# TinyPICO_FeatherWing.net
KiCad netlist of a schematic drawn in EAGLE
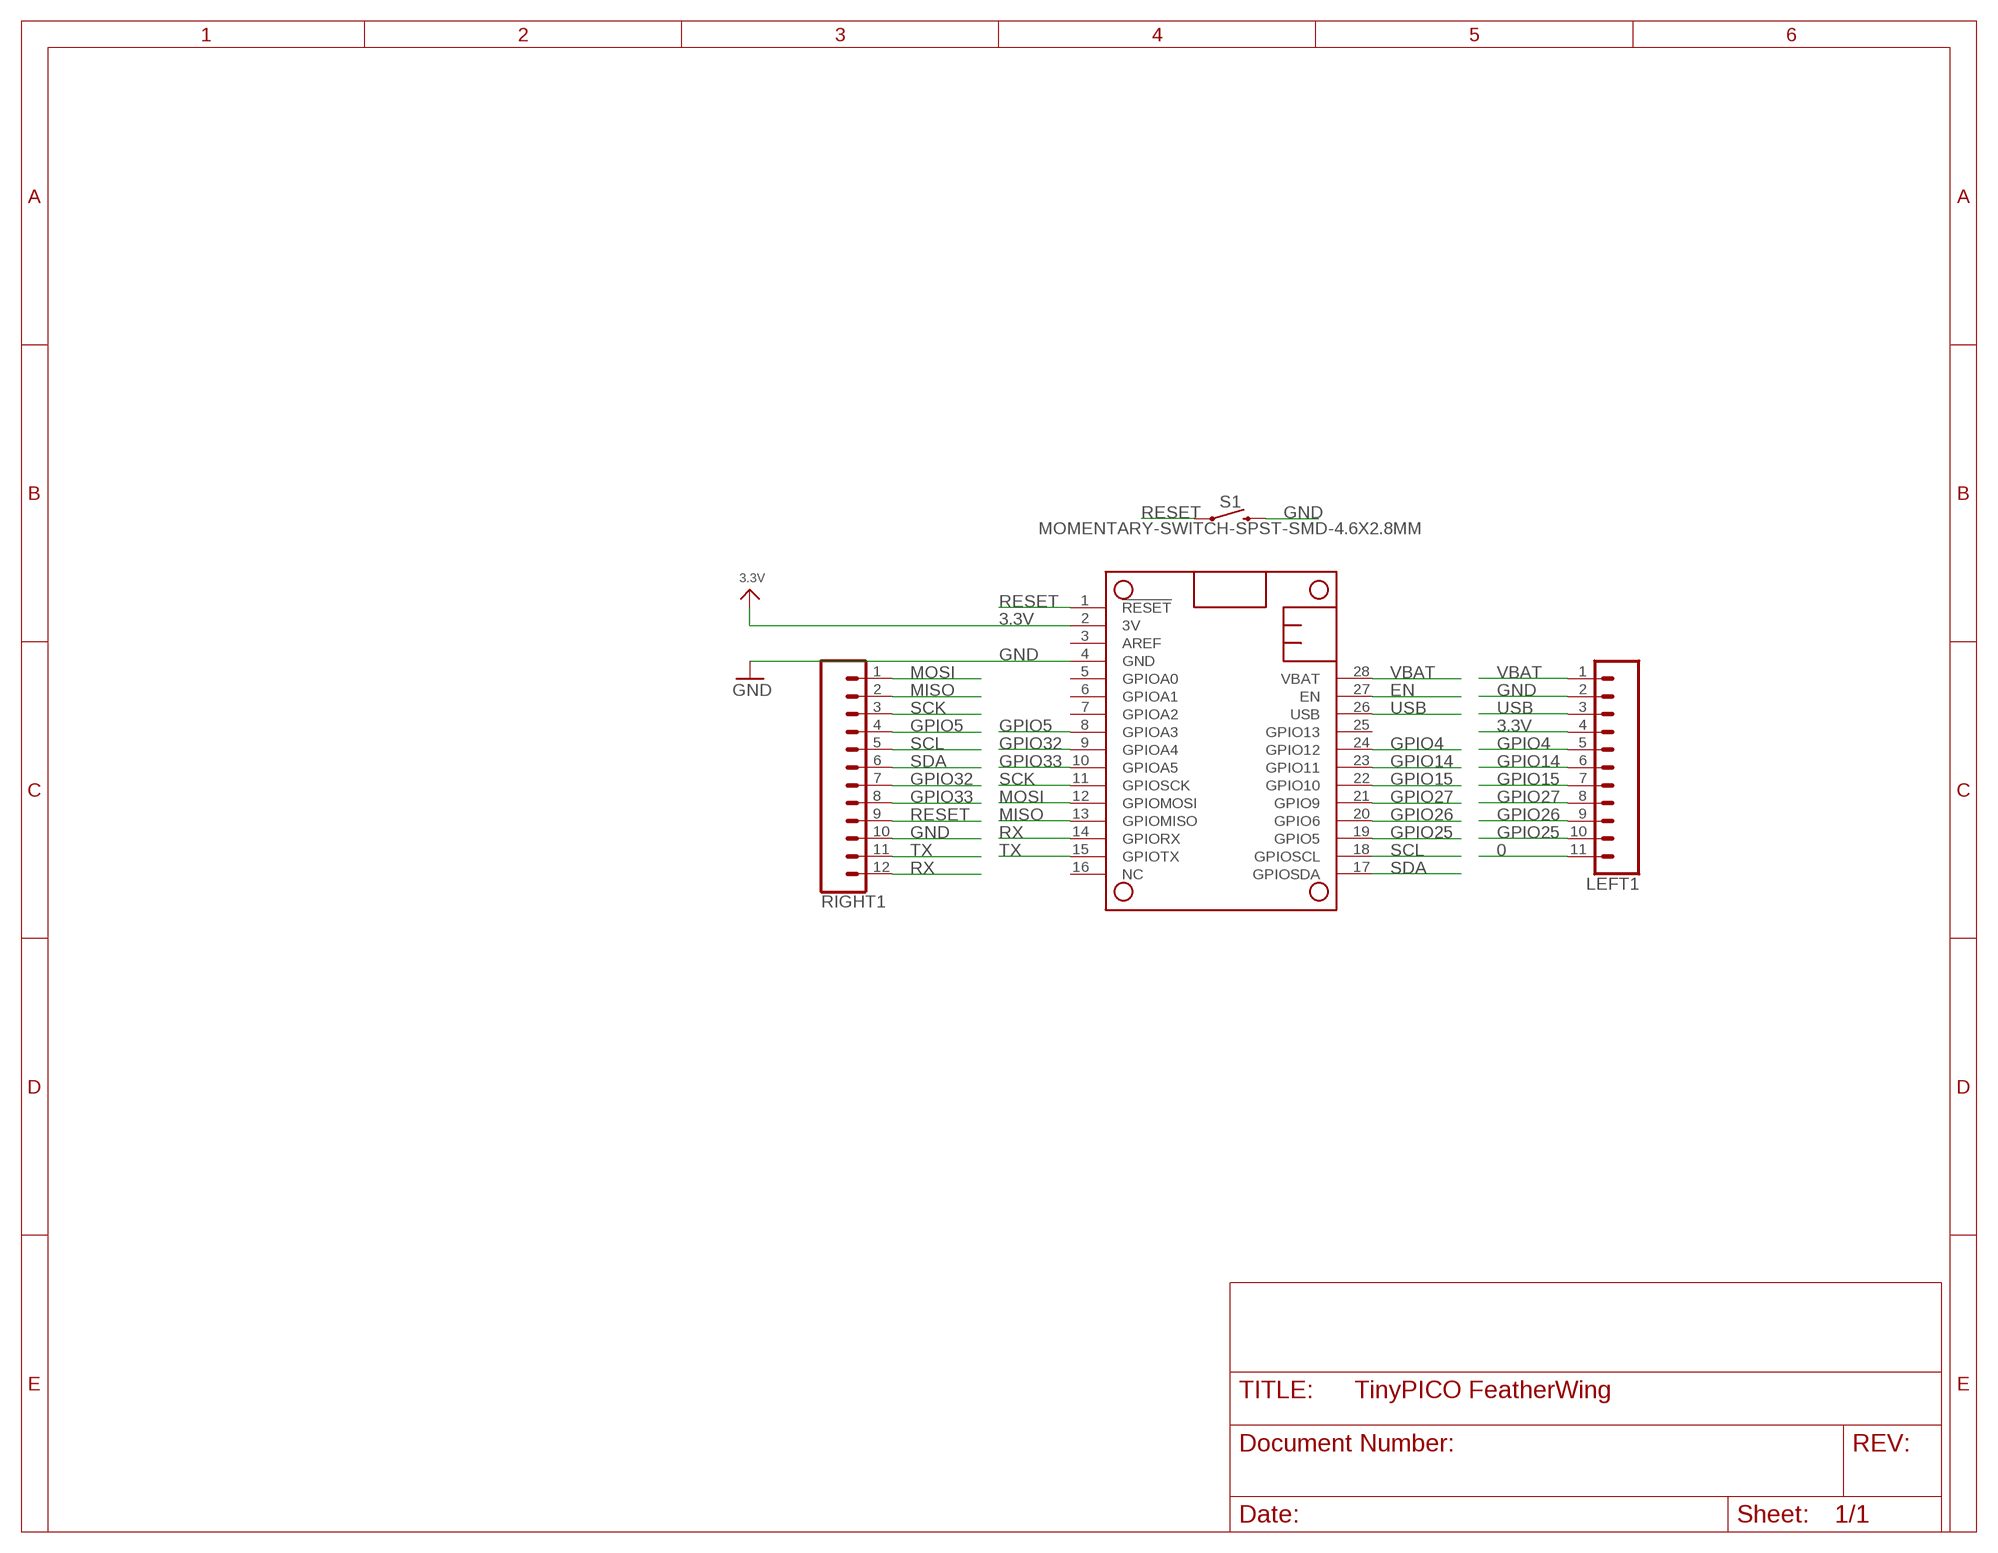
[diagram p0: schematic, sheet 1]

(export (version "E")
  (design (tool "Eeschema 10.0.6"))
  (components
    (comp (ref "LEFT1")
      (value "CONN_11")
      (footprint "eagle-import:1X11")
      (libsource (lib "eagle-import") (part "CONN_11"))
    )
    (comp (ref "MS2")
      (value "FEATHERWING")
      (footprint "eagle-import:FEATHERWING")
      (libsource (lib "eagle-import") (part "FEATHERWING"))
    )
    (comp (ref "RIGHT1")
      (value "CONN_12")
      (footprint "eagle-import:1X12")
      (libsource (lib "eagle-import") (part "CONN_12"))
    )
    (comp (ref "S1")
      (value "MOMENTARY-SWITCH-SPST-SMD-4.6X2.8MM")
      (footprint "eagle-import:TACTILE_SWITCH_SMD_4.6X2.8MM")
      (libsource (lib "eagle-import") (part "MOMENTARY-SWITCH-SPST-SMD-4.6X2.8MM"))
    )
  )
  (nets
    (net (code "1") (name "/0") (class "Default")
      (node (ref "LEFT1") (pin "11") (pinfunction "11_11") (pintype "passive"))
    )
    (net (code "2") (name "/EN") (class "Default")
      (node (ref "MS2") (pin "27") (pinfunction "EN_27") (pintype "passive"))
    )
    (net (code "3") (name "/GPIO4") (class "Default")
      (node (ref "LEFT1") (pin "5") (pinfunction "5_5") (pintype "passive"))
      (node (ref "MS2") (pin "24") (pinfunction "GPIO12_24") (pintype "bidirectional"))
    )
    (net (code "4") (name "/GPIO5") (class "Default")
      (node (ref "MS2") (pin "8") (pinfunction "GPIOA3_8") (pintype "bidirectional"))
      (node (ref "RIGHT1") (pin "4") (pinfunction "4_4") (pintype "passive"))
    )
    (net (code "5") (name "/GPIO14") (class "Default")
      (node (ref "LEFT1") (pin "6") (pinfunction "6_6") (pintype "passive"))
      (node (ref "MS2") (pin "23") (pinfunction "GPIO11_23") (pintype "bidirectional"))
    )
    (net (code "6") (name "/GPIO15") (class "Default")
      (node (ref "LEFT1") (pin "7") (pinfunction "7_7") (pintype "passive"))
      (node (ref "MS2") (pin "22") (pinfunction "GPIO10_22") (pintype "bidirectional"))
    )
    (net (code "7") (name "/GPIO25") (class "Default")
      (node (ref "LEFT1") (pin "10") (pinfunction "10_10") (pintype "passive"))
      (node (ref "MS2") (pin "19") (pinfunction "GPIO5_19") (pintype "bidirectional"))
    )
    (net (code "8") (name "/GPIO26") (class "Default")
      (node (ref "LEFT1") (pin "9") (pinfunction "9_9") (pintype "passive"))
      (node (ref "MS2") (pin "20") (pinfunction "GPIO6_20") (pintype "bidirectional"))
    )
    (net (code "9") (name "/GPIO27") (class "Default")
      (node (ref "LEFT1") (pin "8") (pinfunction "8_8") (pintype "passive"))
      (node (ref "MS2") (pin "21") (pinfunction "GPIO9_21") (pintype "bidirectional"))
    )
    (net (code "10") (name "/GPIO32") (class "Default")
      (node (ref "MS2") (pin "9") (pinfunction "GPIOA4_9") (pintype "bidirectional"))
      (node (ref "RIGHT1") (pin "7") (pinfunction "7_7") (pintype "passive"))
    )
    (net (code "11") (name "/GPIO33") (class "Default")
      (node (ref "MS2") (pin "10") (pinfunction "GPIOA5_10") (pintype "bidirectional"))
      (node (ref "RIGHT1") (pin "8") (pinfunction "8_8") (pintype "passive"))
    )
    (net (code "12") (name "/MISO") (class "Default")
      (node (ref "MS2") (pin "13") (pinfunction "GPIOMISO_13") (pintype "bidirectional"))
      (node (ref "RIGHT1") (pin "2") (pinfunction "2_2") (pintype "passive"))
    )
    (net (code "13") (name "/MOSI") (class "Default")
      (node (ref "MS2") (pin "12") (pinfunction "GPIOMOSI_12") (pintype "bidirectional"))
      (node (ref "RIGHT1") (pin "1") (pinfunction "1_1") (pintype "passive"))
    )
    (net (code "14") (name "/RESET") (class "Default")
      (node (ref "MS2") (pin "1") (pinfunction "~{RESET}_1") (pintype "input"))
      (node (ref "RIGHT1") (pin "9") (pinfunction "9_9") (pintype "passive"))
      (node (ref "S1") (pin "1") (pinfunction "1_1") (pintype "passive"))
      (node (ref "S1") (pin "2") (pinfunction "1_2") (pintype "passive"))
    )
    (net (code "15") (name "/RX") (class "Default")
      (node (ref "MS2") (pin "14") (pinfunction "GPIORX_14") (pintype "bidirectional"))
      (node (ref "RIGHT1") (pin "12") (pinfunction "12_12") (pintype "passive"))
    )
    (net (code "16") (name "/SCK") (class "Default")
      (node (ref "MS2") (pin "11") (pinfunction "GPIOSCK_11") (pintype "bidirectional"))
      (node (ref "RIGHT1") (pin "3") (pinfunction "3_3") (pintype "passive"))
    )
    (net (code "17") (name "/SCL") (class "Default")
      (node (ref "MS2") (pin "18") (pinfunction "GPIOSCL_18") (pintype "bidirectional"))
      (node (ref "RIGHT1") (pin "5") (pinfunction "5_5") (pintype "passive"))
    )
    (net (code "18") (name "/SDA") (class "Default")
      (node (ref "MS2") (pin "17") (pinfunction "GPIOSDA_17") (pintype "bidirectional"))
      (node (ref "RIGHT1") (pin "6") (pinfunction "6_6") (pintype "passive"))
    )
    (net (code "19") (name "/TX") (class "Default")
      (node (ref "MS2") (pin "15") (pinfunction "GPIOTX_15") (pintype "bidirectional"))
      (node (ref "RIGHT1") (pin "11") (pinfunction "11_11") (pintype "passive"))
    )
    (net (code "20") (name "/USB") (class "Default")
      (node (ref "LEFT1") (pin "3") (pinfunction "3_3") (pintype "passive"))
      (node (ref "MS2") (pin "26") (pinfunction "USB_26") (pintype "power_in"))
    )
    (net (code "21") (name "/VBAT") (class "Default")
      (node (ref "LEFT1") (pin "1") (pinfunction "1_1") (pintype "passive"))
      (node (ref "MS2") (pin "28") (pinfunction "VBAT_28") (pintype "power_in"))
    )
    (net (code "22") (name "3.3V") (class "Default")
      (node (ref "LEFT1") (pin "4") (pinfunction "4_4") (pintype "passive"))
      (node (ref "MS2") (pin "2") (pinfunction "3V_2") (pintype "power_in"))
    )
    (net (code "23") (name "GND") (class "Default")
      (node (ref "LEFT1") (pin "2") (pinfunction "2_2") (pintype "passive"))
      (node (ref "MS2") (pin "4") (pinfunction "GND_4") (pintype "power_in"))
      (node (ref "RIGHT1") (pin "10") (pinfunction "10_10") (pintype "passive"))
      (node (ref "S1") (pin "3") (pinfunction "2_3") (pintype "passive"))
      (node (ref "S1") (pin "4") (pinfunction "2_4") (pintype "passive"))
    )
    (net (code "24") (name "unconnected-(MS2-AREF-Pad3)") (class "Default")
      (node (ref "MS2") (pin "3") (pinfunction "AREF_3") (pintype "passive"))
    )
    (net (code "25") (name "unconnected-(MS2-GPIO13-Pad25)") (class "Default")
      (node (ref "MS2") (pin "25") (pinfunction "GPIO13_25") (pintype "bidirectional"))
    )
    (net (code "26") (name "unconnected-(MS2-GPIOA0-Pad5)") (class "Default")
      (node (ref "MS2") (pin "5") (pinfunction "GPIOA0_5") (pintype "bidirectional"))
    )
    (net (code "27") (name "unconnected-(MS2-GPIOA1-Pad6)") (class "Default")
      (node (ref "MS2") (pin "6") (pinfunction "GPIOA1_6") (pintype "bidirectional"))
    )
    (net (code "28") (name "unconnected-(MS2-GPIOA2-Pad7)") (class "Default")
      (node (ref "MS2") (pin "7") (pinfunction "GPIOA2_7") (pintype "bidirectional"))
    )
    (net (code "29") (name "unconnected-(MS2-NC-Pad16)") (class "Default")
      (node (ref "MS2") (pin "16") (pinfunction "NC_16") (pintype "passive"))
    )
  )
)
